# 1-Schematic_SAE301.net
KiCad netlist of a schematic drawn in EasyEDA
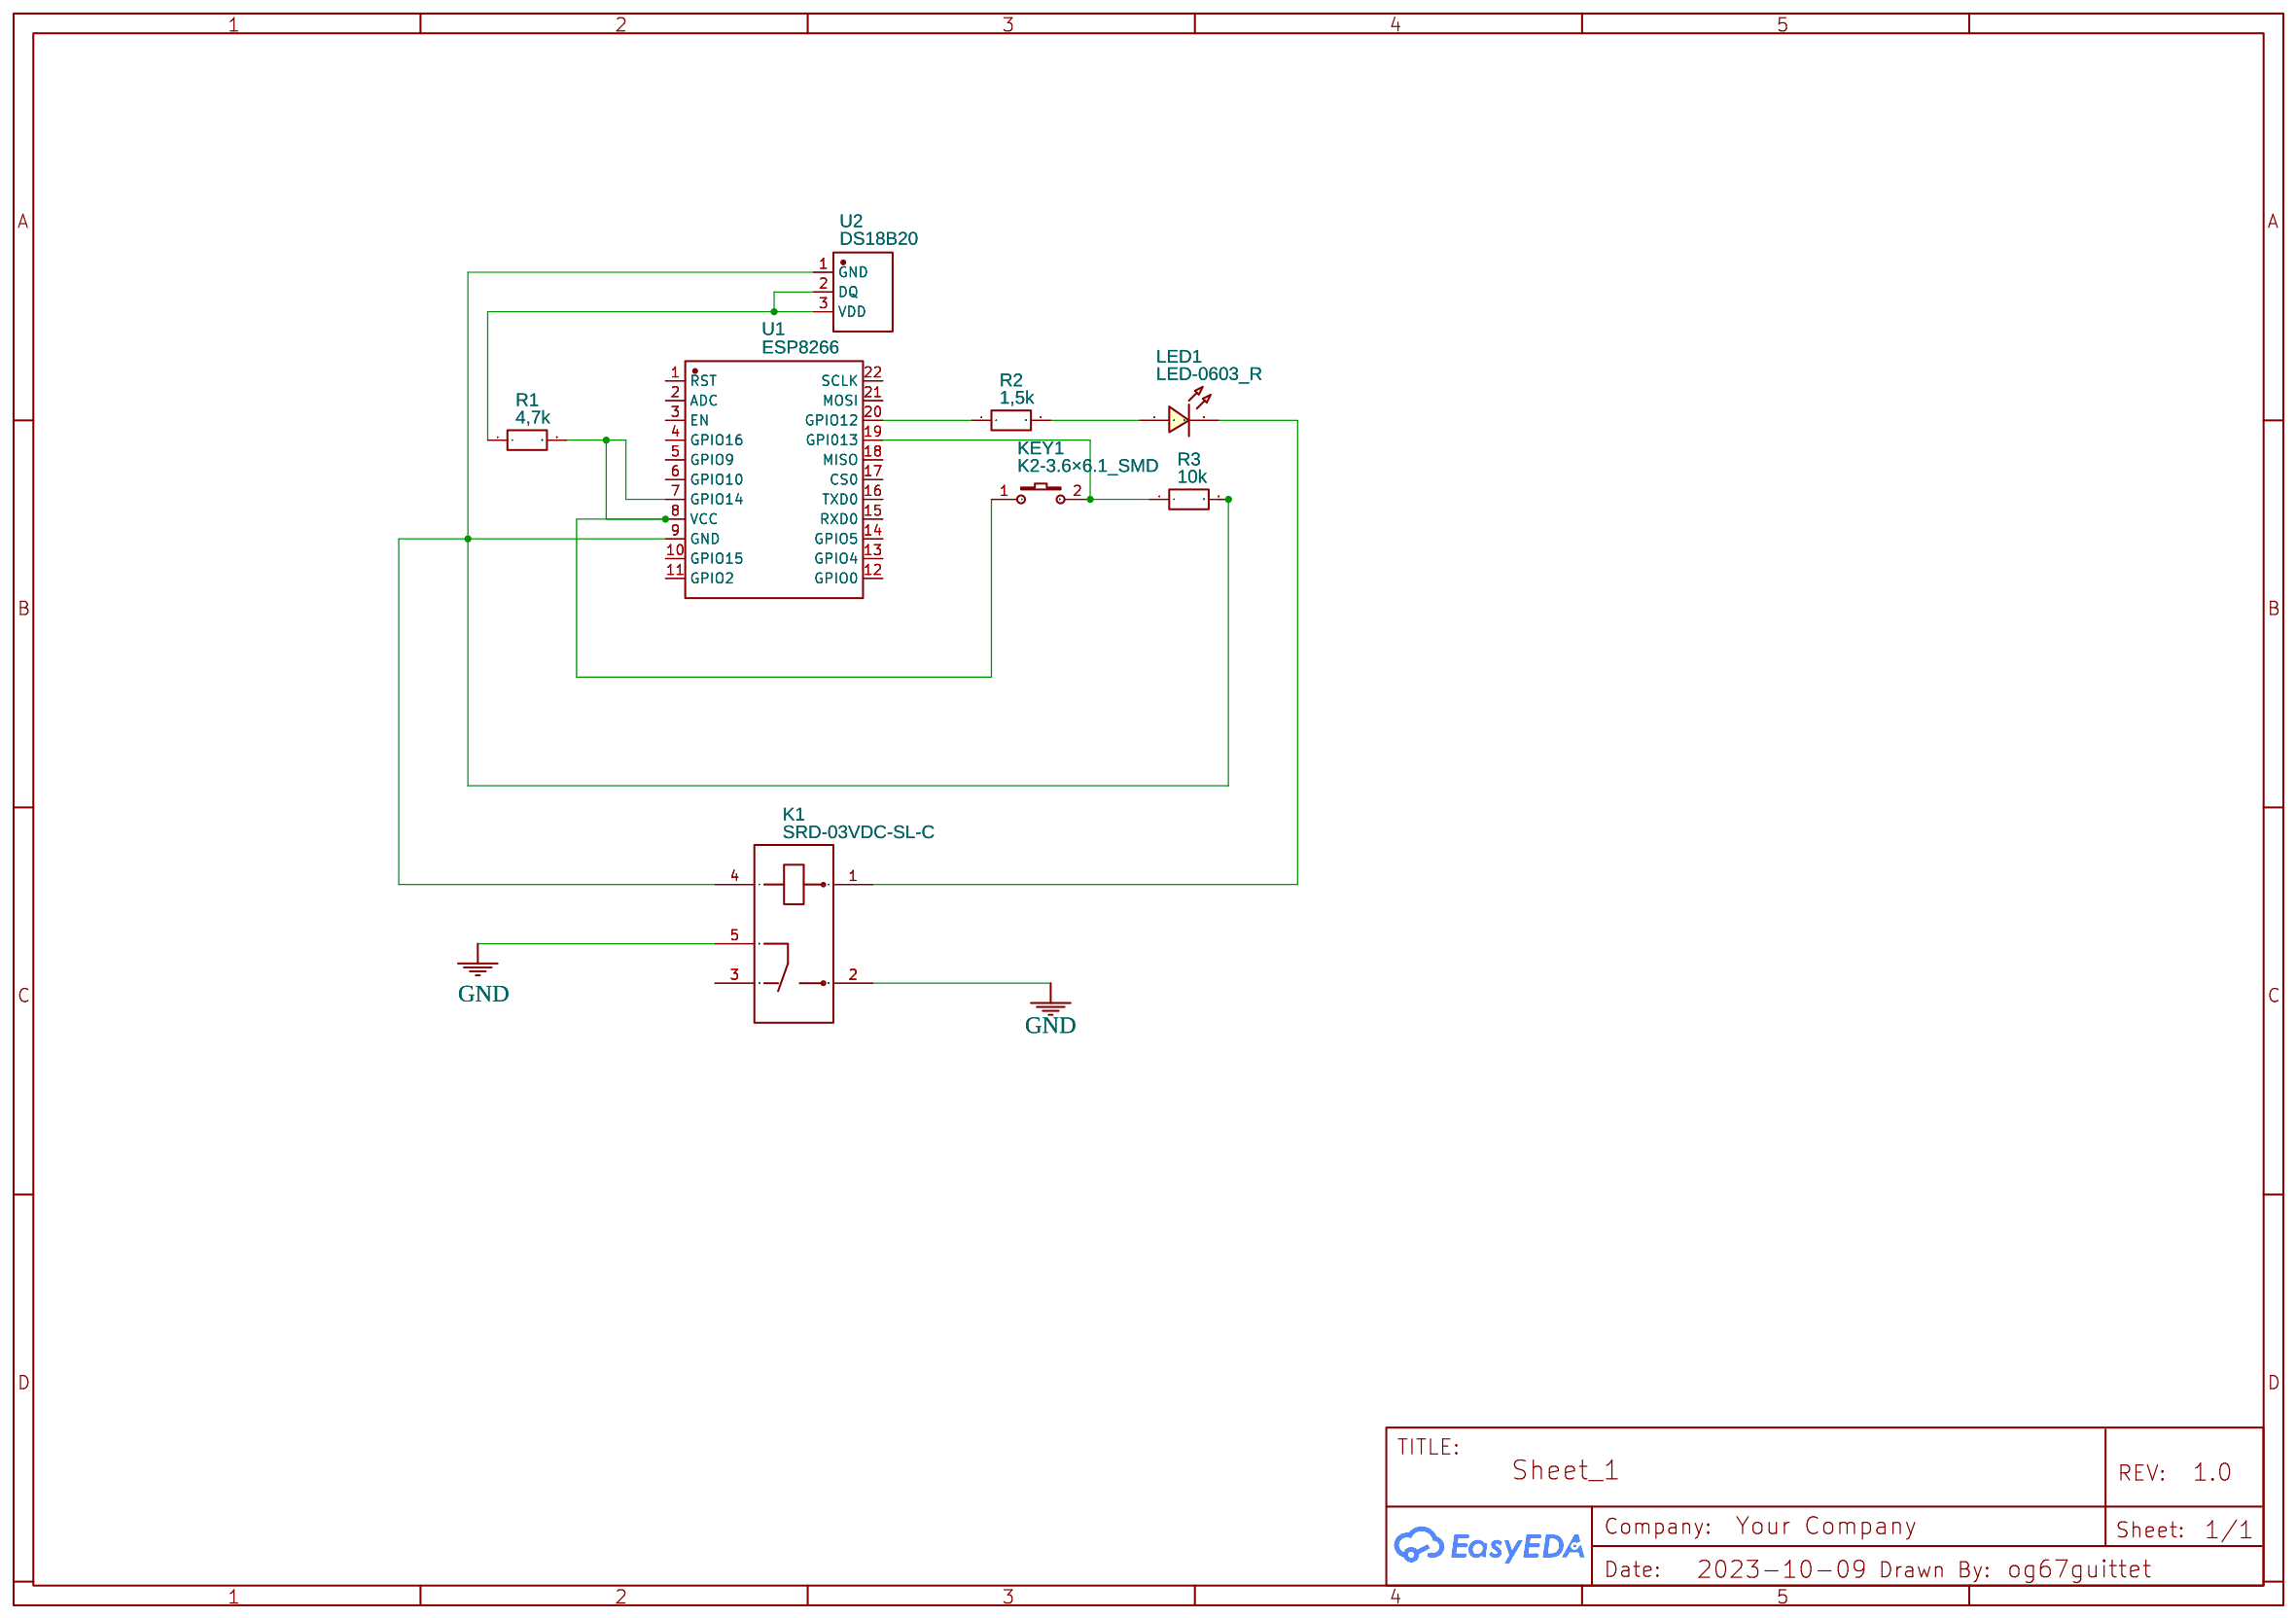
[diagram p0: schematic sheet]

(export (version "E")
  (design (tool "Eeschema 10.0.6"))
  (components
    (comp (ref "K1")
      (value "SRD-03VDC-SL-C")
      (fields (field (name "Manufacturer") "松乐"))
      (libsource (lib "") (part "SRD-03VDC-SL-C"))
    )
    (comp (ref "KEY1")
      (value "K2-3.6×6.1_SMD")
      (fields (field (name "Manufacturer Part") "K2-1107ST-A4SW-06"))
      (libsource (lib "") (part "K2-3.6×6.1_SMD"))
    )
    (comp (ref "LED1")
      (value "LED-0603_R")
      (fields
        (field (name "Manufacturer Part") "19-217/R6C-AL1M2VY/3T")
        (field (name "Manufacturer") "EVERLIGHT(台湾亿光)")
      )
      (libsource (lib "") (part "LED-0603_R"))
    )
    (comp (ref "R1") (value "4,7k") (libsource (lib "") (part "R_0603_EU")))
    (comp (ref "R2") (value "1,5k") (libsource (lib "") (part "R_0603_EU")))
    (comp (ref "R3") (value "10k") (libsource (lib "") (part "R_0603_EU")))
    (comp (ref "U1") (value "ESP8266") (libsource (lib "") (part "ESP8266")))
    (comp (ref "U2")
      (value "DS18B20")
      (fields (field (name "Manufacturer") "UMW(广东友台半导体)"))
      (libsource (lib "") (part "DS18B20"))
    )
  )
  (nets
    (net (code "1") (name "GND") (class "Default")
      (node (ref "K1") (pin "2") (pinfunction "2_2") (pintype "unspecified"))
      (node (ref "K1") (pin "5") (pinfunction "5_5") (pintype "unspecified"))
    )
    (net (code "2") (name "Net-(K1-Pad1)") (class "Default")
      (node (ref "K1") (pin "1") (pinfunction "1_1") (pintype "unspecified"))
      (node (ref "LED1") (pin "2") (pinfunction "2_2") (pintype "unspecified"))
    )
    (net (code "3") (name "Net-(LED1-Pad1)") (class "Default")
      (node (ref "LED1") (pin "1") (pinfunction "1_1") (pintype "unspecified"))
      (node (ref "R2") (pin "2") (pinfunction "2_2") (pintype "unspecified"))
    )
    (net (code "4") (name "Net-(U1-GND)") (class "Default")
      (node (ref "K1") (pin "4") (pinfunction "4_4") (pintype "unspecified"))
      (node (ref "R3") (pin "2") (pinfunction "2_2") (pintype "unspecified"))
      (node (ref "U1") (pin "9") (pinfunction "GND_9") (pintype "unspecified"))
      (node (ref "U2") (pin "1") (pinfunction "GND_1") (pintype "unspecified"))
    )
    (net (code "5") (name "Net-(U1-GPI013)") (class "Default")
      (node (ref "KEY1") (pin "2") (pinfunction "2_2") (pintype "unspecified"))
      (node (ref "R3") (pin "1") (pinfunction "1_1") (pintype "unspecified"))
      (node (ref "U1") (pin "19") (pinfunction "GPI013_19") (pintype "unspecified"))
    )
    (net (code "6") (name "Net-(U1-GPIO12)") (class "Default")
      (node (ref "R2") (pin "1") (pinfunction "1_1") (pintype "unspecified"))
      (node (ref "U1") (pin "20") (pinfunction "GPIO12_20") (pintype "unspecified"))
    )
    (net (code "7") (name "Net-(U1-GPIO14)") (class "Default")
      (node (ref "KEY1") (pin "1") (pinfunction "1_1") (pintype "unspecified"))
      (node (ref "R1") (pin "2") (pinfunction "2_2") (pintype "unspecified"))
      (node (ref "U1") (pin "7") (pinfunction "GPIO14_7") (pintype "unspecified"))
      (node (ref "U1") (pin "8") (pinfunction "VCC_8") (pintype "unspecified"))
    )
    (net (code "8") (name "Net-(U2-DQ)") (class "Default")
      (node (ref "R1") (pin "1") (pinfunction "1_1") (pintype "unspecified"))
      (node (ref "U2") (pin "2") (pinfunction "DQ_2") (pintype "unspecified"))
      (node (ref "U2") (pin "3") (pinfunction "VDD_3") (pintype "unspecified"))
    )
    (net (code "9") (name "unconnected-(K1-Pad3)") (class "Default")
      (node (ref "K1") (pin "3") (pinfunction "3_3") (pintype "unspecified"))
    )
    (net (code "10") (name "unconnected-(U1-ADC-Pad2)") (class "Default")
      (node (ref "U1") (pin "2") (pinfunction "ADC_2") (pintype "unspecified"))
    )
    (net (code "11") (name "unconnected-(U1-CS0-Pad17)") (class "Default")
      (node (ref "U1") (pin "17") (pinfunction "CS0_17") (pintype "unspecified"))
    )
    (net (code "12") (name "unconnected-(U1-EN-Pad3)") (class "Default")
      (node (ref "U1") (pin "3") (pinfunction "EN_3") (pintype "unspecified"))
    )
    (net (code "13") (name "unconnected-(U1-GPIO0-Pad12)") (class "Default")
      (node (ref "U1") (pin "12") (pinfunction "GPIO0_12") (pintype "unspecified"))
    )
    (net (code "14") (name "unconnected-(U1-GPIO2-Pad11)") (class "Default")
      (node (ref "U1") (pin "11") (pinfunction "GPIO2_11") (pintype "unspecified"))
    )
    (net (code "15") (name "unconnected-(U1-GPIO4-Pad13)") (class "Default")
      (node (ref "U1") (pin "13") (pinfunction "GPIO4_13") (pintype "unspecified"))
    )
    (net (code "16") (name "unconnected-(U1-GPIO5-Pad14)") (class "Default")
      (node (ref "U1") (pin "14") (pinfunction "GPIO5_14") (pintype "unspecified"))
    )
    (net (code "17") (name "unconnected-(U1-GPIO9-Pad5)") (class "Default")
      (node (ref "U1") (pin "5") (pinfunction "GPIO9_5") (pintype "unspecified"))
    )
    (net (code "18") (name "unconnected-(U1-GPIO10-Pad6)") (class "Default")
      (node (ref "U1") (pin "6") (pinfunction "GPIO10_6") (pintype "unspecified"))
    )
    (net (code "19") (name "unconnected-(U1-GPIO15-Pad10)") (class "Default")
      (node (ref "U1") (pin "10") (pinfunction "GPIO15_10") (pintype "unspecified"))
    )
    (net (code "20") (name "unconnected-(U1-GPIO16-Pad4)") (class "Default")
      (node (ref "U1") (pin "4") (pinfunction "GPIO16_4") (pintype "unspecified"))
    )
    (net (code "21") (name "unconnected-(U1-MISO-Pad18)") (class "Default")
      (node (ref "U1") (pin "18") (pinfunction "MISO_18") (pintype "unspecified"))
    )
    (net (code "22") (name "unconnected-(U1-MOSI-Pad21)") (class "Default")
      (node (ref "U1") (pin "21") (pinfunction "MOSI_21") (pintype "unspecified"))
    )
    (net (code "23") (name "unconnected-(U1-RST-Pad1)") (class "Default")
      (node (ref "U1") (pin "1") (pinfunction "RST_1") (pintype "unspecified"))
    )
    (net (code "24") (name "unconnected-(U1-RXD0-Pad15)") (class "Default")
      (node (ref "U1") (pin "15") (pinfunction "RXD0_15") (pintype "unspecified"))
    )
    (net (code "25") (name "unconnected-(U1-SCLK-Pad22)") (class "Default")
      (node (ref "U1") (pin "22") (pinfunction "SCLK_22") (pintype "unspecified"))
    )
    (net (code "26") (name "unconnected-(U1-TXD0-Pad16)") (class "Default")
      (node (ref "U1") (pin "16") (pinfunction "TXD0_16") (pintype "unspecified"))
    )
  )
)
